# mega328.net
KiCad netlist of a schematic drawn in EAGLE
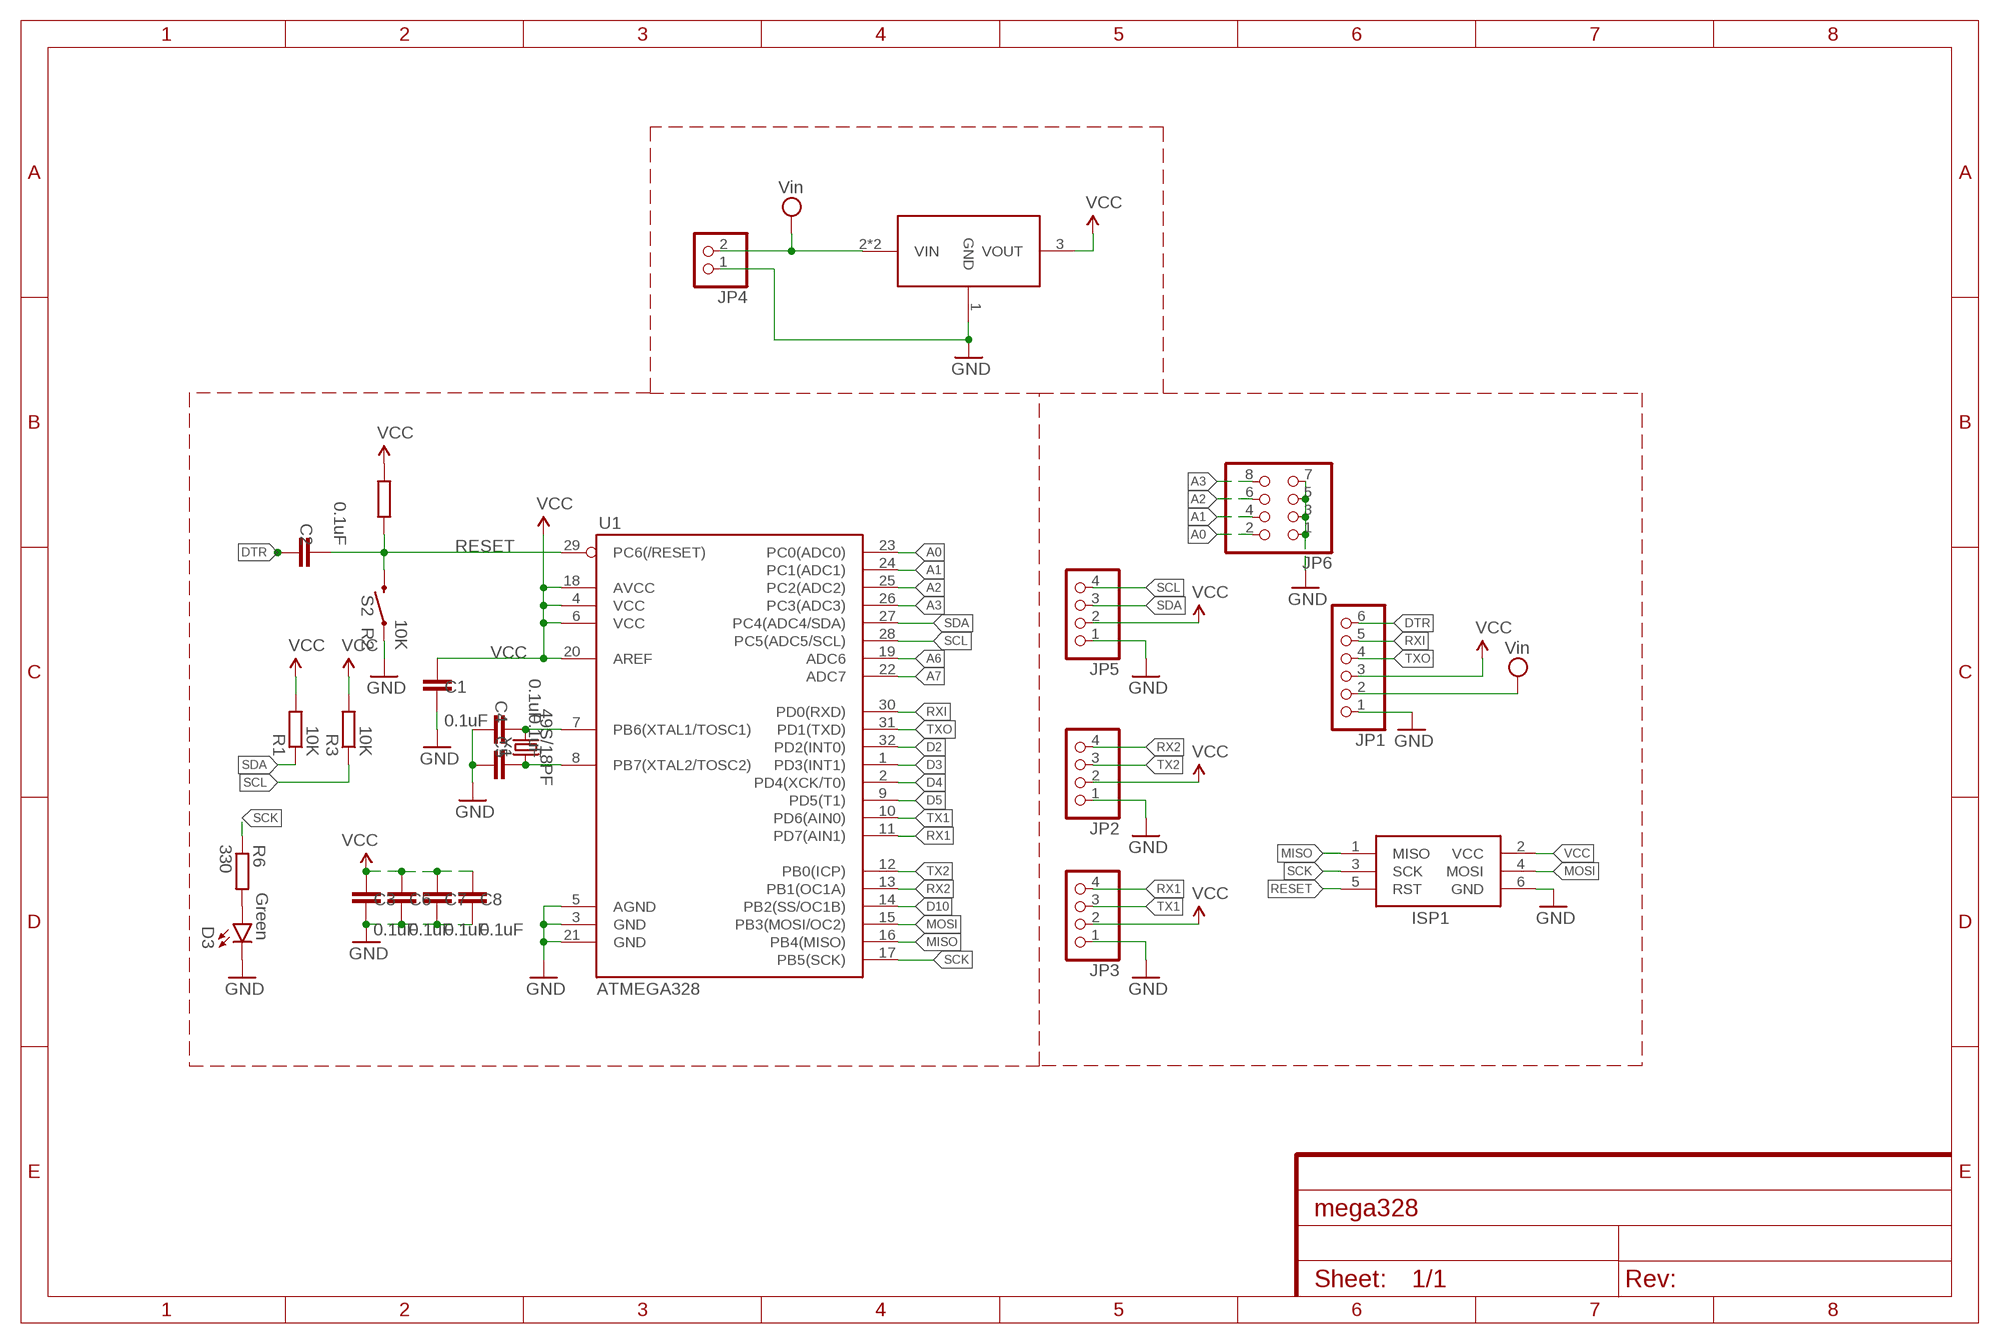
[diagram p0: schematic, sheet 1]

(export (version "E")
  (design (tool "Eeschema 10.0.6"))
  (components
    (comp (ref "C1")
      (value "0.1uF")
      (footprint "eagle-import:C0805")
      (libsource (lib "eagle-import") (part "C-EUC0805"))
    )
    (comp (ref "C2")
      (value "0.1uF")
      (footprint "eagle-import:C0805")
      (libsource (lib "eagle-import") (part "C-EUC0805"))
    )
    (comp (ref "C3")
      (value "0.1uF")
      (footprint "eagle-import:C0805")
      (libsource (lib "eagle-import") (part "C-EUC0805"))
    )
    (comp (ref "C4")
      (value "0.1uF")
      (footprint "eagle-import:C0805")
      (libsource (lib "eagle-import") (part "C-EUC0805"))
    )
    (comp (ref "C5")
      (value "0.1uF")
      (footprint "eagle-import:C0805")
      (libsource (lib "eagle-import") (part "C-EUC0805"))
    )
    (comp (ref "C6")
      (value "0.1uF")
      (footprint "eagle-import:C0805")
      (libsource (lib "eagle-import") (part "C-EUC0805"))
    )
    (comp (ref "C7")
      (value "0.1uF")
      (footprint "eagle-import:C0805")
      (libsource (lib "eagle-import") (part "C-EUC0805"))
    )
    (comp (ref "C8")
      (value "0.1uF")
      (footprint "eagle-import:C0805")
      (libsource (lib "eagle-import") (part "C-EUC0805"))
    )
    (comp (ref "D3")
      (value "Green")
      (footprint "eagle-import:CHIP-LED0805")
      (libsource (lib "eagle-import") (part "LEDCHIP-LED0805"))
    )
    (comp (ref "ISP1")
      (value "AVRISP3D")
      (footprint "eagle-import:2X03")
      (libsource (lib "eagle-import") (part "AVRISP3D"))
    )
    (comp (ref "JP1")
      (value "PINHD-1X06_2.54-S")
      (footprint "eagle-import:1X06")
      (libsource (lib "eagle-import") (part "PINHD-1X06_2.54-S"))
    )
    (comp (ref "JP2")
      (value "PINHD-1X04_2.54-S")
      (footprint "eagle-import:1X04-S")
      (libsource (lib "eagle-import") (part "PINHD-1X04_2.54-S"))
    )
    (comp (ref "JP3")
      (value "PINHD-1X04_2.54-S")
      (footprint "eagle-import:1X04-S")
      (libsource (lib "eagle-import") (part "PINHD-1X04_2.54-S"))
    )
    (comp (ref "JP4")
      (value "PINHD-1X02_2.54-S")
      (footprint "eagle-import:1X02-S")
      (libsource (lib "eagle-import") (part "PINHD-1X02_2.54-S"))
    )
    (comp (ref "JP5")
      (value "PINHD-1X04_2.54-S")
      (footprint "eagle-import:1X04-S")
      (libsource (lib "eagle-import") (part "PINHD-1X04_2.54-S"))
    )
    (comp (ref "JP6")
      (value "PINHD-2X4")
      (footprint "eagle-import:2X04")
      (libsource (lib "eagle-import") (part "PINHD-2X4"))
    )
    (comp (ref "R1")
      (value "10K")
      (footprint "eagle-import:R0805")
      (libsource (lib "eagle-import") (part "R-EU_R0805"))
    )
    (comp (ref "R2")
      (value "10K")
      (footprint "eagle-import:R0805")
      (libsource (lib "eagle-import") (part "R-EU_R0805"))
    )
    (comp (ref "R3")
      (value "10K")
      (footprint "eagle-import:R0805")
      (libsource (lib "eagle-import") (part "R-EU_R0805"))
    )
    (comp (ref "R6")
      (value "330")
      (footprint "eagle-import:R0805")
      (libsource (lib "eagle-import") (part "R-EU_R0805"))
    )
    (comp (ref "S2")
      (value "MOMENTARY-SWITCH-SPST-PTH-6.0MM")
      (footprint "eagle-import:TACTILE_SWITCH_PTH_6.0MM")
      (libsource (lib "eagle-import") (part "MOMENTARY-SWITCH-SPST-PTH-6.0MM"))
    )
    (comp (ref "U$1")
      (value "AIC1722A-33PXATR")
      (footprint "eagle-import:SOT89")
      (libsource (lib "eagle-import") (part "AIC1722A-33PXATR"))
    )
    (comp (ref "U1")
      (value "ATMEGA328")
      (footprint "eagle-import:TQFP32-08")
      (libsource (lib "eagle-import") (part "ATMEGA168"))
    )
    (comp (ref "Y1")
      (value "49S/18PF")
      (footprint "eagle-import:XTAL_HC49")
      (fields (field (name "MANUFACTURER") "Xinhunjing ") (field (name "CREATED_BY") "PCBLayout.com"))
      (libsource (lib "eagle-import") (part "49S/18PF"))
    )
  )
  (nets
    (net (code "1") (name "A0") (class "Default")
      (node (ref "JP6") (pin "2") (pinfunction "2_2") (pintype "passive"))
      (node (ref "U1") (pin "23") (pinfunction "PC0(ADC0)_23") (pintype "bidirectional"))
    )
    (net (code "2") (name "A1") (class "Default")
      (node (ref "JP6") (pin "4") (pinfunction "4_4") (pintype "passive"))
      (node (ref "U1") (pin "24") (pinfunction "PC1(ADC1)_24") (pintype "bidirectional"))
    )
    (net (code "3") (name "A2") (class "Default")
      (node (ref "JP6") (pin "6") (pinfunction "6_6") (pintype "passive"))
      (node (ref "U1") (pin "25") (pinfunction "PC2(ADC2)_25") (pintype "bidirectional"))
    )
    (net (code "4") (name "A3") (class "Default")
      (node (ref "JP6") (pin "8") (pinfunction "8_8") (pintype "passive"))
      (node (ref "U1") (pin "26") (pinfunction "PC3(ADC3)_26") (pintype "bidirectional"))
    )
    (net (code "5") (name "A6") (class "Default")
      (node (ref "U1") (pin "19") (pinfunction "ADC6_19") (pintype "bidirectional"))
    )
    (net (code "6") (name "A7") (class "Default")
      (node (ref "U1") (pin "22") (pinfunction "ADC7_22") (pintype "bidirectional"))
    )
    (net (code "7") (name "D2") (class "Default")
      (node (ref "U1") (pin "32") (pinfunction "PD2(INT0)_32") (pintype "bidirectional"))
    )
    (net (code "8") (name "D3") (class "Default")
      (node (ref "U1") (pin "1") (pinfunction "PD3(INT1)_1") (pintype "bidirectional"))
    )
    (net (code "9") (name "D4") (class "Default")
      (node (ref "U1") (pin "2") (pinfunction "PD4(XCK/T0)_2") (pintype "bidirectional"))
    )
    (net (code "10") (name "D5") (class "Default")
      (node (ref "U1") (pin "9") (pinfunction "PD5(T1)_9") (pintype "bidirectional"))
    )
    (net (code "11") (name "D10") (class "Default")
      (node (ref "U1") (pin "14") (pinfunction "PB2(SS/OC1B)_14") (pintype "bidirectional"))
    )
    (net (code "12") (name "DTR") (class "Default")
      (node (ref "C2") (pin "2") (pinfunction "2_2") (pintype "passive"))
      (node (ref "JP1") (pin "6") (pinfunction "6_6") (pintype "passive"))
    )
    (net (code "13") (name "GND") (class "Default")
      (node (ref "C1") (pin "1") (pinfunction "1_1") (pintype "passive"))
      (node (ref "C3") (pin "1") (pinfunction "1_1") (pintype "passive"))
      (node (ref "C4") (pin "2") (pinfunction "2_2") (pintype "passive"))
      (node (ref "C5") (pin "2") (pinfunction "2_2") (pintype "passive"))
      (node (ref "C6") (pin "1") (pinfunction "1_1") (pintype "passive"))
      (node (ref "C7") (pin "1") (pinfunction "1_1") (pintype "passive"))
      (node (ref "C8") (pin "1") (pinfunction "1_1") (pintype "passive"))
      (node (ref "D3") (pin "C") (pinfunction "C_C") (pintype "passive"))
      (node (ref "ISP1") (pin "6") (pinfunction "GND_6") (pintype "power_in"))
      (node (ref "JP1") (pin "1") (pinfunction "1_1") (pintype "passive"))
      (node (ref "JP2") (pin "1") (pinfunction "1_1") (pintype "passive"))
      (node (ref "JP3") (pin "1") (pinfunction "1_1") (pintype "passive"))
      (node (ref "JP4") (pin "1") (pinfunction "1_1") (pintype "passive"))
      (node (ref "JP5") (pin "1") (pinfunction "1_1") (pintype "passive"))
      (node (ref "JP6") (pin "1") (pinfunction "1_1") (pintype "passive"))
      (node (ref "JP6") (pin "3") (pinfunction "3_3") (pintype "passive"))
      (node (ref "JP6") (pin "5") (pinfunction "5_5") (pintype "passive"))
      (node (ref "JP6") (pin "7") (pinfunction "7_7") (pintype "passive"))
      (node (ref "S2") (pin "1") (pinfunction "1_1") (pintype "passive"))
      (node (ref "S2") (pin "2") (pinfunction "1_2") (pintype "passive"))
      (node (ref "U$1") (pin "1") (pinfunction "GND_1") (pintype "bidirectional"))
      (node (ref "U1") (pin "21") (pinfunction "GND_21") (pintype "bidirectional"))
      (node (ref "U1") (pin "3") (pinfunction "GND_3") (pintype "bidirectional"))
      (node (ref "U1") (pin "5") (pinfunction "AGND_5") (pintype "bidirectional"))
    )
    (net (code "14") (name "MISO") (class "Default")
      (node (ref "ISP1") (pin "1") (pinfunction "MISO_1") (pintype "input"))
      (node (ref "U1") (pin "16") (pinfunction "PB4(MISO)_16") (pintype "bidirectional"))
    )
    (net (code "15") (name "MOSI") (class "Default")
      (node (ref "ISP1") (pin "4") (pinfunction "MOSI_4") (pintype "output"))
      (node (ref "U1") (pin "15") (pinfunction "PB3(MOSI/OC2)_15") (pintype "bidirectional"))
    )
    (net (code "16") (name "Net-(D3-PadA)") (class "Default")
      (node (ref "D3") (pin "A") (pinfunction "A_A") (pintype "passive"))
      (node (ref "R6") (pin "2") (pinfunction "2_2") (pintype "passive"))
    )
    (net (code "17") (name "Net-(U1-PB6(XTAL1{slash}TOSC1))") (class "Default")
      (node (ref "C4") (pin "1") (pinfunction "1_1") (pintype "passive"))
      (node (ref "U1") (pin "7") (pinfunction "PB6(XTAL1/TOSC1)_7") (pintype "bidirectional"))
      (node (ref "Y1") (pin "2") (pinfunction "2_2") (pintype "passive"))
    )
    (net (code "18") (name "Net-(U1-PB7(XTAL2{slash}TOSC2))") (class "Default")
      (node (ref "C5") (pin "1") (pinfunction "1_1") (pintype "passive"))
      (node (ref "U1") (pin "8") (pinfunction "PB7(XTAL2/TOSC2)_8") (pintype "bidirectional"))
      (node (ref "Y1") (pin "1") (pinfunction "1_1") (pintype "passive"))
    )
    (net (code "19") (name "RESET") (class "Default")
      (node (ref "C2") (pin "1") (pinfunction "1_1") (pintype "passive"))
      (node (ref "ISP1") (pin "5") (pinfunction "RST_5") (pintype "output"))
      (node (ref "R2") (pin "1") (pinfunction "1_1") (pintype "passive"))
      (node (ref "S2") (pin "3") (pinfunction "2_3") (pintype "passive"))
      (node (ref "S2") (pin "4") (pinfunction "2_4") (pintype "passive"))
      (node (ref "U1") (pin "29") (pinfunction "PC6(/RESET)_29") (pintype "bidirectional"))
    )
    (net (code "20") (name "RX1") (class "Default")
      (node (ref "JP3") (pin "4") (pinfunction "4_4") (pintype "passive"))
      (node (ref "U1") (pin "11") (pinfunction "PD7(AIN1)_11") (pintype "bidirectional"))
    )
    (net (code "21") (name "RX2") (class "Default")
      (node (ref "JP2") (pin "4") (pinfunction "4_4") (pintype "passive"))
      (node (ref "U1") (pin "13") (pinfunction "PB1(OC1A)_13") (pintype "bidirectional"))
    )
    (net (code "22") (name "RXI") (class "Default")
      (node (ref "JP1") (pin "5") (pinfunction "5_5") (pintype "passive"))
      (node (ref "U1") (pin "30") (pinfunction "PD0(RXD)_30") (pintype "bidirectional"))
    )
    (net (code "23") (name "SCK") (class "Default")
      (node (ref "ISP1") (pin "3") (pinfunction "SCK_3") (pintype "output"))
      (node (ref "R6") (pin "1") (pinfunction "1_1") (pintype "passive"))
      (node (ref "U1") (pin "17") (pinfunction "PB5(SCK)_17") (pintype "bidirectional"))
    )
    (net (code "24") (name "SCL") (class "Default")
      (node (ref "JP5") (pin "4") (pinfunction "4_4") (pintype "passive"))
      (node (ref "R3") (pin "1") (pinfunction "1_1") (pintype "passive"))
      (node (ref "U1") (pin "28") (pinfunction "PC5(ADC5/SCL)_28") (pintype "bidirectional"))
    )
    (net (code "25") (name "SDA") (class "Default")
      (node (ref "JP5") (pin "3") (pinfunction "3_3") (pintype "passive"))
      (node (ref "R1") (pin "1") (pinfunction "1_1") (pintype "passive"))
      (node (ref "U1") (pin "27") (pinfunction "PC4(ADC4/SDA)_27") (pintype "bidirectional"))
    )
    (net (code "26") (name "TX1") (class "Default")
      (node (ref "JP3") (pin "3") (pinfunction "3_3") (pintype "passive"))
      (node (ref "U1") (pin "10") (pinfunction "PD6(AIN0)_10") (pintype "bidirectional"))
    )
    (net (code "27") (name "TX2") (class "Default")
      (node (ref "JP2") (pin "3") (pinfunction "3_3") (pintype "passive"))
      (node (ref "U1") (pin "12") (pinfunction "PB0(ICP)_12") (pintype "bidirectional"))
    )
    (net (code "28") (name "TXO") (class "Default")
      (node (ref "JP1") (pin "4") (pinfunction "4_4") (pintype "passive"))
      (node (ref "U1") (pin "31") (pinfunction "PD1(TXD)_31") (pintype "bidirectional"))
    )
    (net (code "29") (name "VCC") (class "Default")
      (node (ref "C1") (pin "2") (pinfunction "2_2") (pintype "passive"))
      (node (ref "C3") (pin "2") (pinfunction "2_2") (pintype "passive"))
      (node (ref "C6") (pin "2") (pinfunction "2_2") (pintype "passive"))
      (node (ref "C7") (pin "2") (pinfunction "2_2") (pintype "passive"))
      (node (ref "C8") (pin "2") (pinfunction "2_2") (pintype "passive"))
      (node (ref "ISP1") (pin "2") (pinfunction "VCC_2") (pintype "power_in"))
      (node (ref "JP1") (pin "3") (pinfunction "3_3") (pintype "passive"))
      (node (ref "JP2") (pin "2") (pinfunction "2_2") (pintype "passive"))
      (node (ref "JP3") (pin "2") (pinfunction "2_2") (pintype "passive"))
      (node (ref "JP5") (pin "2") (pinfunction "2_2") (pintype "passive"))
      (node (ref "R1") (pin "2") (pinfunction "2_2") (pintype "passive"))
      (node (ref "R2") (pin "2") (pinfunction "2_2") (pintype "passive"))
      (node (ref "R3") (pin "2") (pinfunction "2_2") (pintype "passive"))
      (node (ref "U$1") (pin "3") (pinfunction "VOUT_3") (pintype "bidirectional"))
      (node (ref "U1") (pin "18") (pinfunction "AVCC_18") (pintype "bidirectional"))
      (node (ref "U1") (pin "20") (pinfunction "AREF_20") (pintype "bidirectional"))
      (node (ref "U1") (pin "4") (pinfunction "VCC_4") (pintype "bidirectional"))
      (node (ref "U1") (pin "6") (pinfunction "VCC_6") (pintype "bidirectional"))
    )
    (net (code "30") (name "Vin") (class "Default")
      (node (ref "JP1") (pin "2") (pinfunction "2_2") (pintype "passive"))
      (node (ref "JP4") (pin "2") (pinfunction "2_2") (pintype "passive"))
      (node (ref "U$1") (pin "2") (pinfunction "VIN_2") (pintype "bidirectional"))
      (node (ref "U$1") (pin "2@1") (pinfunction "VIN_2@1") (pintype "bidirectional"))
    )
  )
)
